# Mechanical.net
KiCad netlist of a schematic drawn in Altium Designer
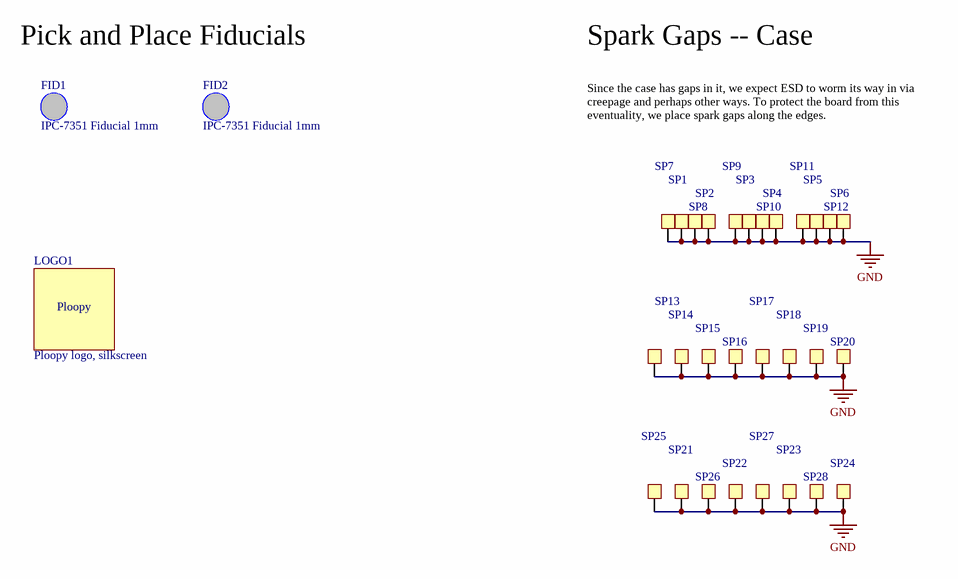
[diagram p0: Mechanical.SchDoc]

(export (version "E")
  (design (tool "Eeschema 10.0.6"))
  (components
    (comp (ref "FID1")
      (value "IPC-7351 Fiducial 1mm")
      (footprint "FIDUCIAL_1.5")
      (libsource (lib "Mechanical") (part "FIDUCIAL_1.5"))
    )
    (comp (ref "FID2")
      (value "IPC-7351 Fiducial 1mm")
      (footprint "FIDUCIAL_1.5")
      (libsource (lib "Mechanical") (part "FIDUCIAL_1.5"))
    )
    (comp (ref "LOGO1")
      (value "Ploopy logo, silkscreen")
      (footprint "PloopyLogo")
      (libsource (lib "Graphics") (part "PloopyLogo"))
    )
    (comp (ref "SP1")
      (value "Spark Gap")
      (footprint "SparkGap")
      (description "Open square pad for spark gapping")
      (libsource (lib "PCBFeatures") (part "Spark Gap"))
    )
    (comp (ref "SP2")
      (value "Spark Gap")
      (footprint "SparkGap")
      (description "Open square pad for spark gapping")
      (libsource (lib "PCBFeatures") (part "Spark Gap"))
    )
    (comp (ref "SP3")
      (value "Spark Gap")
      (footprint "SparkGap")
      (description "Open square pad for spark gapping")
      (libsource (lib "PCBFeatures") (part "Spark Gap"))
    )
    (comp (ref "SP4")
      (value "Spark Gap")
      (footprint "SparkGap")
      (description "Open square pad for spark gapping")
      (libsource (lib "PCBFeatures") (part "Spark Gap"))
    )
    (comp (ref "SP5")
      (value "Spark Gap")
      (footprint "SparkGap")
      (description "Open square pad for spark gapping")
      (libsource (lib "PCBFeatures") (part "Spark Gap"))
    )
    (comp (ref "SP6")
      (value "Spark Gap")
      (footprint "SparkGap")
      (description "Open square pad for spark gapping")
      (libsource (lib "PCBFeatures") (part "Spark Gap"))
    )
    (comp (ref "SP7")
      (value "Spark Gap")
      (footprint "SparkGap")
      (description "Open square pad for spark gapping")
      (libsource (lib "PCBFeatures") (part "Spark Gap"))
    )
    (comp (ref "SP8")
      (value "Spark Gap")
      (footprint "SparkGap")
      (description "Open square pad for spark gapping")
      (libsource (lib "PCBFeatures") (part "Spark Gap"))
    )
    (comp (ref "SP9")
      (value "Spark Gap")
      (footprint "SparkGap")
      (description "Open square pad for spark gapping")
      (libsource (lib "PCBFeatures") (part "Spark Gap"))
    )
    (comp (ref "SP10")
      (value "Spark Gap")
      (footprint "SparkGap")
      (description "Open square pad for spark gapping")
      (libsource (lib "PCBFeatures") (part "Spark Gap"))
    )
    (comp (ref "SP11")
      (value "Spark Gap")
      (footprint "SparkGap")
      (description "Open square pad for spark gapping")
      (libsource (lib "PCBFeatures") (part "Spark Gap"))
    )
    (comp (ref "SP12")
      (value "Spark Gap")
      (footprint "SparkGap")
      (description "Open square pad for spark gapping")
      (libsource (lib "PCBFeatures") (part "Spark Gap"))
    )
    (comp (ref "SP13")
      (value "Spark Gap")
      (footprint "SparkGap")
      (description "Open square pad for spark gapping")
      (libsource (lib "PCBFeatures") (part "Spark Gap"))
    )
    (comp (ref "SP14")
      (value "Spark Gap")
      (footprint "SparkGap")
      (description "Open square pad for spark gapping")
      (libsource (lib "PCBFeatures") (part "Spark Gap"))
    )
    (comp (ref "SP15")
      (value "Spark Gap")
      (footprint "SparkGap")
      (description "Open square pad for spark gapping")
      (libsource (lib "PCBFeatures") (part "Spark Gap"))
    )
    (comp (ref "SP16")
      (value "Spark Gap")
      (footprint "SparkGap")
      (description "Open square pad for spark gapping")
      (libsource (lib "PCBFeatures") (part "Spark Gap"))
    )
    (comp (ref "SP17")
      (value "Spark Gap")
      (footprint "SparkGap")
      (description "Open square pad for spark gapping")
      (libsource (lib "PCBFeatures") (part "Spark Gap"))
    )
    (comp (ref "SP18")
      (value "Spark Gap")
      (footprint "SparkGap")
      (description "Open square pad for spark gapping")
      (libsource (lib "PCBFeatures") (part "Spark Gap"))
    )
    (comp (ref "SP19")
      (value "Spark Gap")
      (footprint "SparkGap")
      (description "Open square pad for spark gapping")
      (libsource (lib "PCBFeatures") (part "Spark Gap"))
    )
    (comp (ref "SP20")
      (value "Spark Gap")
      (footprint "SparkGap")
      (description "Open square pad for spark gapping")
      (libsource (lib "PCBFeatures") (part "Spark Gap"))
    )
    (comp (ref "SP21")
      (value "Spark Gap")
      (footprint "SparkGap")
      (description "Open square pad for spark gapping")
      (libsource (lib "PCBFeatures") (part "Spark Gap"))
    )
    (comp (ref "SP22")
      (value "Spark Gap")
      (footprint "SparkGap")
      (description "Open square pad for spark gapping")
      (libsource (lib "PCBFeatures") (part "Spark Gap"))
    )
    (comp (ref "SP23")
      (value "Spark Gap")
      (footprint "SparkGap")
      (description "Open square pad for spark gapping")
      (libsource (lib "PCBFeatures") (part "Spark Gap"))
    )
    (comp (ref "SP24")
      (value "Spark Gap")
      (footprint "SparkGap")
      (description "Open square pad for spark gapping")
      (libsource (lib "PCBFeatures") (part "Spark Gap"))
    )
    (comp (ref "SP25")
      (value "Spark Gap")
      (footprint "SparkGap")
      (description "Open square pad for spark gapping")
      (libsource (lib "PCBFeatures") (part "Spark Gap"))
    )
    (comp (ref "SP26")
      (value "Spark Gap")
      (footprint "SparkGap")
      (description "Open square pad for spark gapping")
      (libsource (lib "PCBFeatures") (part "Spark Gap"))
    )
    (comp (ref "SP27")
      (value "Spark Gap")
      (footprint "SparkGap")
      (description "Open square pad for spark gapping")
      (libsource (lib "PCBFeatures") (part "Spark Gap"))
    )
    (comp (ref "SP28")
      (value "Spark Gap")
      (footprint "SparkGap")
      (description "Open square pad for spark gapping")
      (libsource (lib "PCBFeatures") (part "Spark Gap"))
    )
  )
  (nets
    (net (code "1") (name "GND") (class "Default")
      (node (ref "SP1") (pin "1") (pinfunction "1_1") (pintype "passive"))
      (node (ref "SP10") (pin "1") (pinfunction "1_1") (pintype "passive"))
      (node (ref "SP11") (pin "1") (pinfunction "1_1") (pintype "passive"))
      (node (ref "SP12") (pin "1") (pinfunction "1_1") (pintype "passive"))
      (node (ref "SP13") (pin "1") (pinfunction "1_1") (pintype "passive"))
      (node (ref "SP14") (pin "1") (pinfunction "1_1") (pintype "passive"))
      (node (ref "SP15") (pin "1") (pinfunction "1_1") (pintype "passive"))
      (node (ref "SP16") (pin "1") (pinfunction "1_1") (pintype "passive"))
      (node (ref "SP17") (pin "1") (pinfunction "1_1") (pintype "passive"))
      (node (ref "SP18") (pin "1") (pinfunction "1_1") (pintype "passive"))
      (node (ref "SP19") (pin "1") (pinfunction "1_1") (pintype "passive"))
      (node (ref "SP2") (pin "1") (pinfunction "1_1") (pintype "passive"))
      (node (ref "SP20") (pin "1") (pinfunction "1_1") (pintype "passive"))
      (node (ref "SP21") (pin "1") (pinfunction "1_1") (pintype "passive"))
      (node (ref "SP22") (pin "1") (pinfunction "1_1") (pintype "passive"))
      (node (ref "SP23") (pin "1") (pinfunction "1_1") (pintype "passive"))
      (node (ref "SP24") (pin "1") (pinfunction "1_1") (pintype "passive"))
      (node (ref "SP25") (pin "1") (pinfunction "1_1") (pintype "passive"))
      (node (ref "SP26") (pin "1") (pinfunction "1_1") (pintype "passive"))
      (node (ref "SP27") (pin "1") (pinfunction "1_1") (pintype "passive"))
      (node (ref "SP28") (pin "1") (pinfunction "1_1") (pintype "passive"))
      (node (ref "SP3") (pin "1") (pinfunction "1_1") (pintype "passive"))
      (node (ref "SP4") (pin "1") (pinfunction "1_1") (pintype "passive"))
      (node (ref "SP5") (pin "1") (pinfunction "1_1") (pintype "passive"))
      (node (ref "SP6") (pin "1") (pinfunction "1_1") (pintype "passive"))
      (node (ref "SP7") (pin "1") (pinfunction "1_1") (pintype "passive"))
      (node (ref "SP8") (pin "1") (pinfunction "1_1") (pintype "passive"))
      (node (ref "SP9") (pin "1") (pinfunction "1_1") (pintype "passive"))
    )
    (net (code "2") (name "unconnected-(FID1-Pad1)") (class "Default")
      (node (ref "FID1") (pin "1") (pinfunction "1_1") (pintype "passive"))
    )
    (net (code "3") (name "unconnected-(FID2-Pad1)") (class "Default")
      (node (ref "FID2") (pin "1") (pinfunction "1_1") (pintype "passive"))
    )
  )
)
